# C64_Keyb-Test-ext.net
KiCad netlist of a schematic drawn in EAGLE
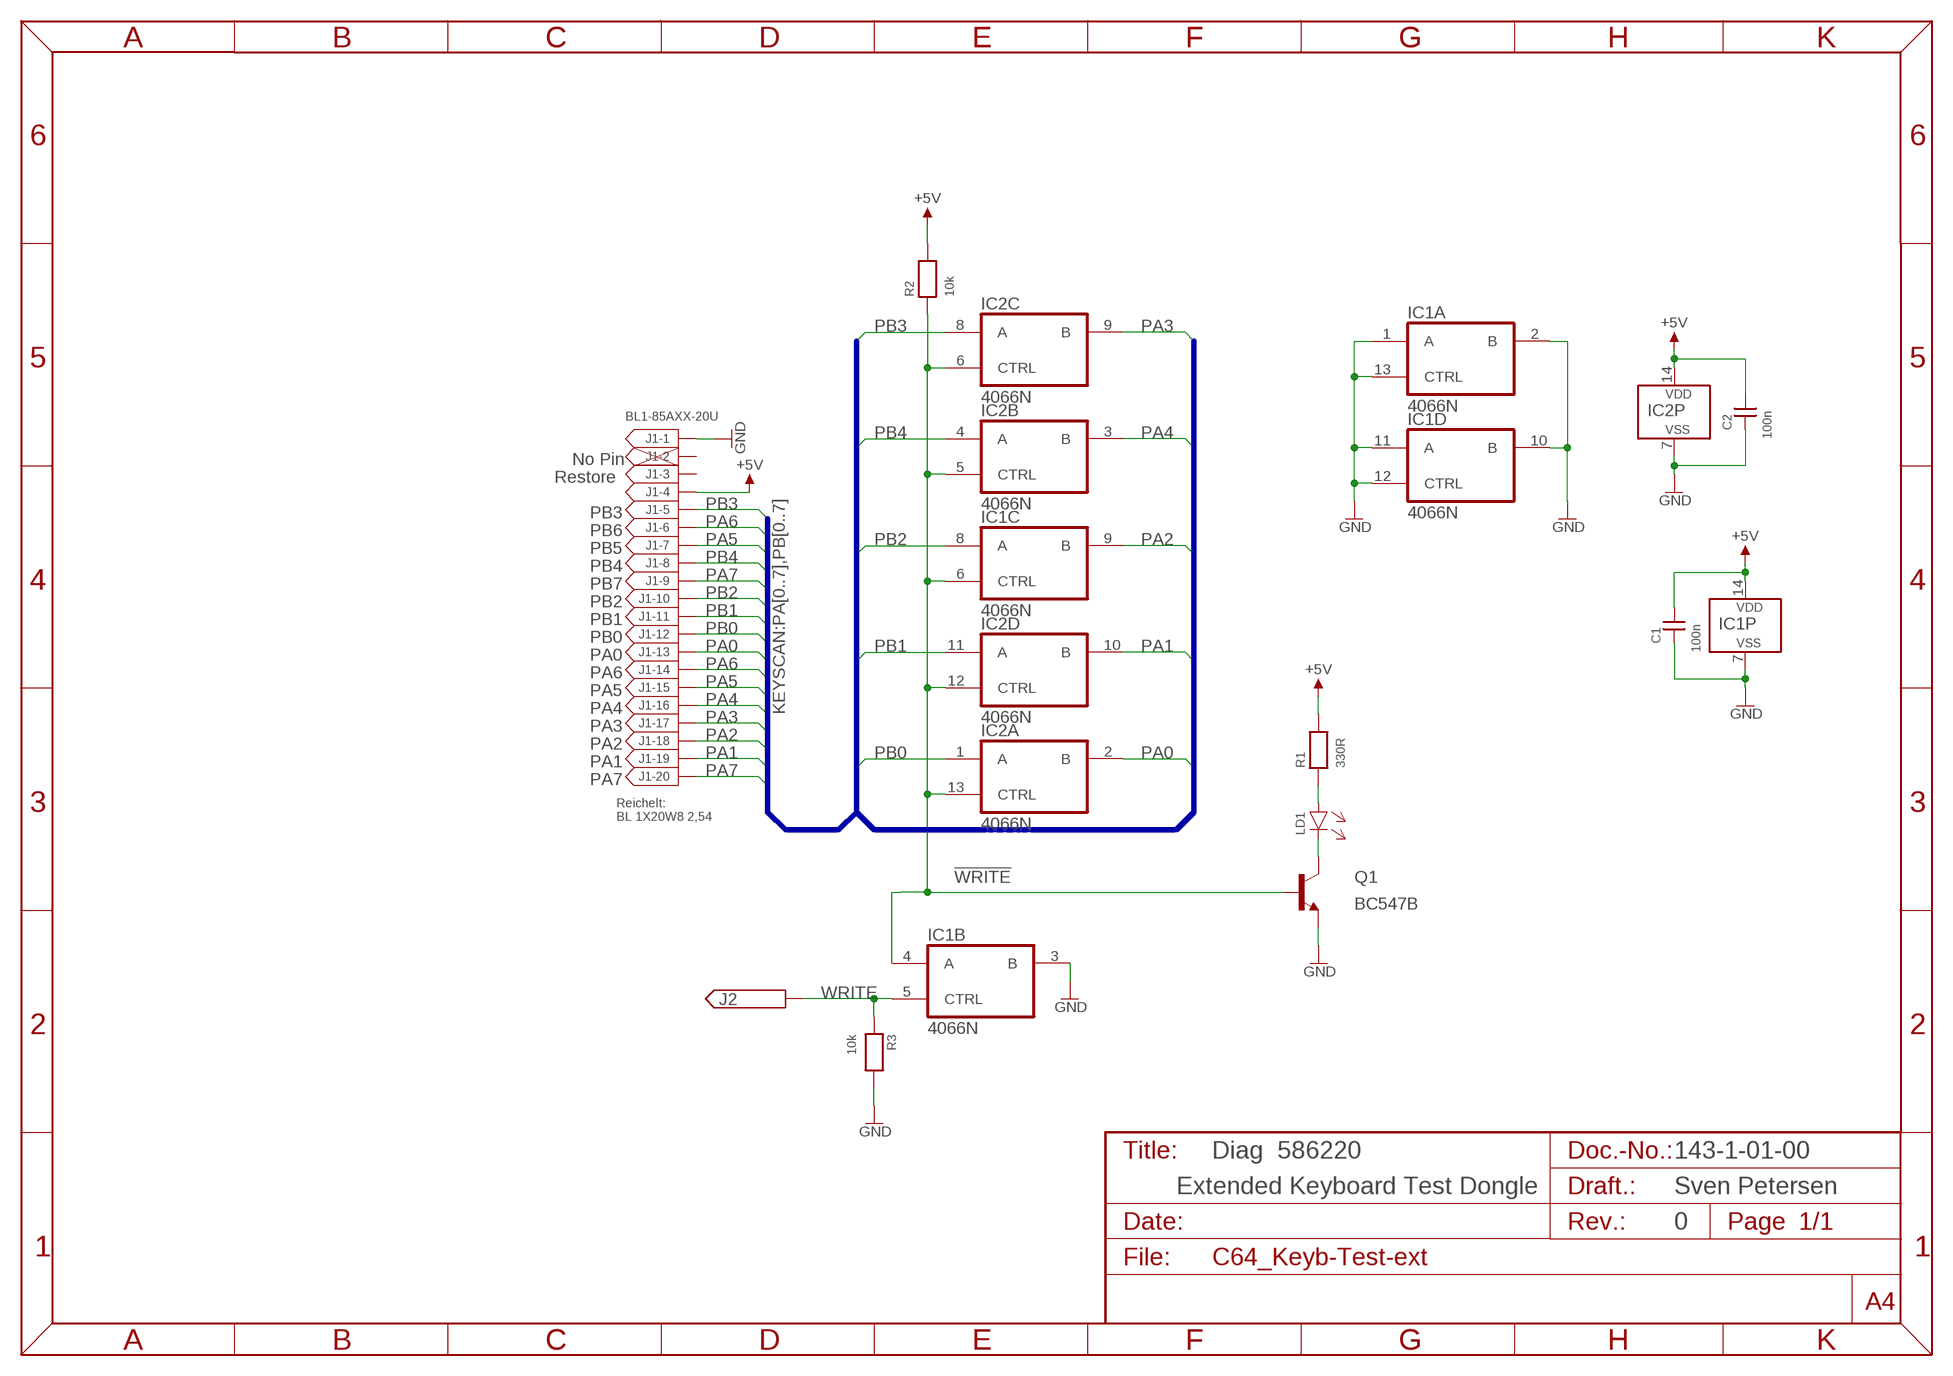
[diagram p0: schematic, sheet 1]

(export (version "E")
  (design (tool "Eeschema 10.0.6"))
  (components
    (comp (ref "C1")
      (value "100n")
      (footprint "eagle-import:C-5")
      (libsource (lib "eagle-import") (part "CAP02"))
    )
    (comp (ref "C2")
      (value "100n")
      (footprint "eagle-import:C-5")
      (libsource (lib "eagle-import") (part "CAP02"))
    )
    (comp (ref "IC1")
      (value "4066N")
      (footprint "eagle-import:DIL14")
      (libsource (lib "eagle-import") (part "4066N"))
    )
    (comp (ref "IC2")
      (value "4066N")
      (footprint "eagle-import:DIL14")
      (libsource (lib "eagle-import") (part "4066N"))
    )
    (comp (ref "J1")
      (value "BL1-85AXX-20U")
      (footprint "eagle-import:BL1-85AXX-20U")
      (libsource (lib "eagle-import") (part "BL1-85AXX-20U"))
    )
    (comp (ref "J2")
      (value "PINHD-1X1")
      (footprint "eagle-import:1X01")
      (libsource (lib "eagle-import") (part "PINHD-1X1"))
    )
    (comp (ref "LD1")
      (value "3MM")
      (footprint "eagle-import:3MM")
      (libsource (lib "eagle-import") (part "3MM"))
    )
    (comp (ref "Q1")
      (value "BC547B")
      (footprint "eagle-import:TO92")
      (libsource (lib "eagle-import") (part "BC547B"))
    )
    (comp (ref "R1")
      (value "330R")
      (footprint "eagle-import:R-10")
      (libsource (lib "eagle-import") (part "RES04"))
    )
    (comp (ref "R2")
      (value "10k")
      (footprint "eagle-import:R-10")
      (libsource (lib "eagle-import") (part "RES04"))
    )
    (comp (ref "R3")
      (value "10k")
      (footprint "eagle-import:R-10")
      (libsource (lib "eagle-import") (part "RES04"))
    )
  )
  (nets
    (net (code "1") (name "+5V") (class "Default")
      (node (ref "C1") (pin "2") (pinfunction "2_2") (pintype "passive"))
      (node (ref "C2") (pin "2") (pinfunction "2_2") (pintype "passive"))
      (node (ref "IC1") (pin "14") (pinfunction "VDD_14") (pintype "power_in"))
      (node (ref "IC2") (pin "14") (pinfunction "VDD_14") (pintype "power_in"))
      (node (ref "J1") (pin "4") (pinfunction "1_4") (pintype "bidirectional"))
      (node (ref "R1") (pin "2") (pinfunction "2_2") (pintype "passive"))
      (node (ref "R2") (pin "2") (pinfunction "2_2") (pintype "passive"))
    )
    (net (code "2") (name "/PA0") (class "Default")
      (node (ref "IC2") (pin "2") (pinfunction "B_2") (pintype "tri_state"))
      (node (ref "J1") (pin "13") (pinfunction "1_13") (pintype "bidirectional"))
    )
    (net (code "3") (name "/PA1") (class "Default")
      (node (ref "IC2") (pin "10") (pinfunction "B_10") (pintype "tri_state"))
      (node (ref "J1") (pin "19") (pinfunction "1_19") (pintype "bidirectional"))
    )
    (net (code "4") (name "/PA2") (class "Default")
      (node (ref "IC1") (pin "9") (pinfunction "B_9") (pintype "tri_state"))
      (node (ref "J1") (pin "18") (pinfunction "1_18") (pintype "bidirectional"))
    )
    (net (code "5") (name "/PA3") (class "Default")
      (node (ref "IC2") (pin "9") (pinfunction "B_9") (pintype "tri_state"))
      (node (ref "J1") (pin "17") (pinfunction "1_17") (pintype "bidirectional"))
    )
    (net (code "6") (name "/PA4") (class "Default")
      (node (ref "IC2") (pin "3") (pinfunction "B_3") (pintype "tri_state"))
      (node (ref "J1") (pin "16") (pinfunction "1_16") (pintype "bidirectional"))
    )
    (net (code "7") (name "/PA5") (class "Default")
      (node (ref "J1") (pin "15") (pinfunction "1_15") (pintype "bidirectional"))
      (node (ref "J1") (pin "7") (pinfunction "1_7") (pintype "bidirectional"))
    )
    (net (code "8") (name "/PA6") (class "Default")
      (node (ref "J1") (pin "14") (pinfunction "1_14") (pintype "bidirectional"))
      (node (ref "J1") (pin "6") (pinfunction "1_6") (pintype "bidirectional"))
    )
    (net (code "9") (name "/PA7") (class "Default")
      (node (ref "J1") (pin "20") (pinfunction "1_20") (pintype "bidirectional"))
      (node (ref "J1") (pin "9") (pinfunction "1_9") (pintype "bidirectional"))
    )
    (net (code "10") (name "/PB0") (class "Default")
      (node (ref "IC2") (pin "1") (pinfunction "A_1") (pintype "tri_state"))
      (node (ref "J1") (pin "12") (pinfunction "1_12") (pintype "bidirectional"))
    )
    (net (code "11") (name "/PB1") (class "Default")
      (node (ref "IC2") (pin "11") (pinfunction "A_11") (pintype "tri_state"))
      (node (ref "J1") (pin "11") (pinfunction "1_11") (pintype "bidirectional"))
    )
    (net (code "12") (name "/PB2") (class "Default")
      (node (ref "IC1") (pin "8") (pinfunction "A_8") (pintype "tri_state"))
      (node (ref "J1") (pin "10") (pinfunction "1_10") (pintype "bidirectional"))
    )
    (net (code "13") (name "/PB3") (class "Default")
      (node (ref "IC2") (pin "8") (pinfunction "A_8") (pintype "tri_state"))
      (node (ref "J1") (pin "5") (pinfunction "1_5") (pintype "bidirectional"))
    )
    (net (code "14") (name "/PB4") (class "Default")
      (node (ref "IC2") (pin "4") (pinfunction "A_4") (pintype "tri_state"))
      (node (ref "J1") (pin "8") (pinfunction "1_8") (pintype "bidirectional"))
    )
    (net (code "15") (name "/WRITE") (class "Default")
      (node (ref "IC1") (pin "5") (pinfunction "CTRL_5") (pintype "input"))
      (node (ref "J2") (pin "1") (pinfunction "1_1") (pintype "passive"))
      (node (ref "R3") (pin "1") (pinfunction "1_1") (pintype "passive"))
    )
    (net (code "17") (name "/~{WRITE}") (class "Default")
      (node (ref "IC1") (pin "4") (pinfunction "A_4") (pintype "tri_state"))
      (node (ref "IC1") (pin "6") (pinfunction "CTRL_6") (pintype "input"))
      (node (ref "IC2") (pin "12") (pinfunction "CTRL_12") (pintype "input"))
      (node (ref "IC2") (pin "13") (pinfunction "CTRL_13") (pintype "input"))
      (node (ref "IC2") (pin "5") (pinfunction "CTRL_5") (pintype "input"))
      (node (ref "IC2") (pin "6") (pinfunction "CTRL_6") (pintype "input"))
      (node (ref "Q1") (pin "2") (pinfunction "B_2") (pintype "passive"))
      (node (ref "R2") (pin "1") (pinfunction "1_1") (pintype "passive"))
    )
    (net (code "18") (name "GND") (class "Default")
      (node (ref "C1") (pin "1") (pinfunction "1_1") (pintype "passive"))
      (node (ref "C2") (pin "1") (pinfunction "1_1") (pintype "passive"))
      (node (ref "IC1") (pin "1") (pinfunction "A_1") (pintype "tri_state"))
      (node (ref "IC1") (pin "10") (pinfunction "B_10") (pintype "tri_state"))
      (node (ref "IC1") (pin "11") (pinfunction "A_11") (pintype "tri_state"))
      (node (ref "IC1") (pin "12") (pinfunction "CTRL_12") (pintype "input"))
      (node (ref "IC1") (pin "13") (pinfunction "CTRL_13") (pintype "input"))
      (node (ref "IC1") (pin "2") (pinfunction "B_2") (pintype "tri_state"))
      (node (ref "IC1") (pin "3") (pinfunction "B_3") (pintype "tri_state"))
      (node (ref "IC1") (pin "7") (pinfunction "VSS_7") (pintype "power_in"))
      (node (ref "IC2") (pin "7") (pinfunction "VSS_7") (pintype "power_in"))
      (node (ref "J1") (pin "1") (pinfunction "1_1") (pintype "bidirectional"))
      (node (ref "Q1") (pin "1") (pinfunction "E_1") (pintype "passive"))
      (node (ref "R3") (pin "2") (pinfunction "2_2") (pintype "passive"))
    )
    (net (code "19") (name "Net-(LD1-K)") (class "Default")
      (node (ref "LD1") (pin "C") (pinfunction "K_C") (pintype "bidirectional"))
      (node (ref "Q1") (pin "3") (pinfunction "C_3") (pintype "passive"))
    )
    (net (code "20") (name "Net-(LD1-PadA)") (class "Default")
      (node (ref "LD1") (pin "A") (pinfunction "A_A") (pintype "bidirectional"))
      (node (ref "R1") (pin "1") (pinfunction "1_1") (pintype "passive"))
    )
    (net (code "21") (name "unconnected-(J1L-1-Pad2)") (class "Default")
      (node (ref "J1") (pin "2") (pinfunction "1_2") (pintype "bidirectional"))
    )
    (net (code "22") (name "unconnected-(J1N-1-Pad3)") (class "Default")
      (node (ref "J1") (pin "3") (pinfunction "1_3") (pintype "bidirectional"))
    )
  )
)
